# Main.net
KiCad netlist of a schematic drawn in Altium Designer
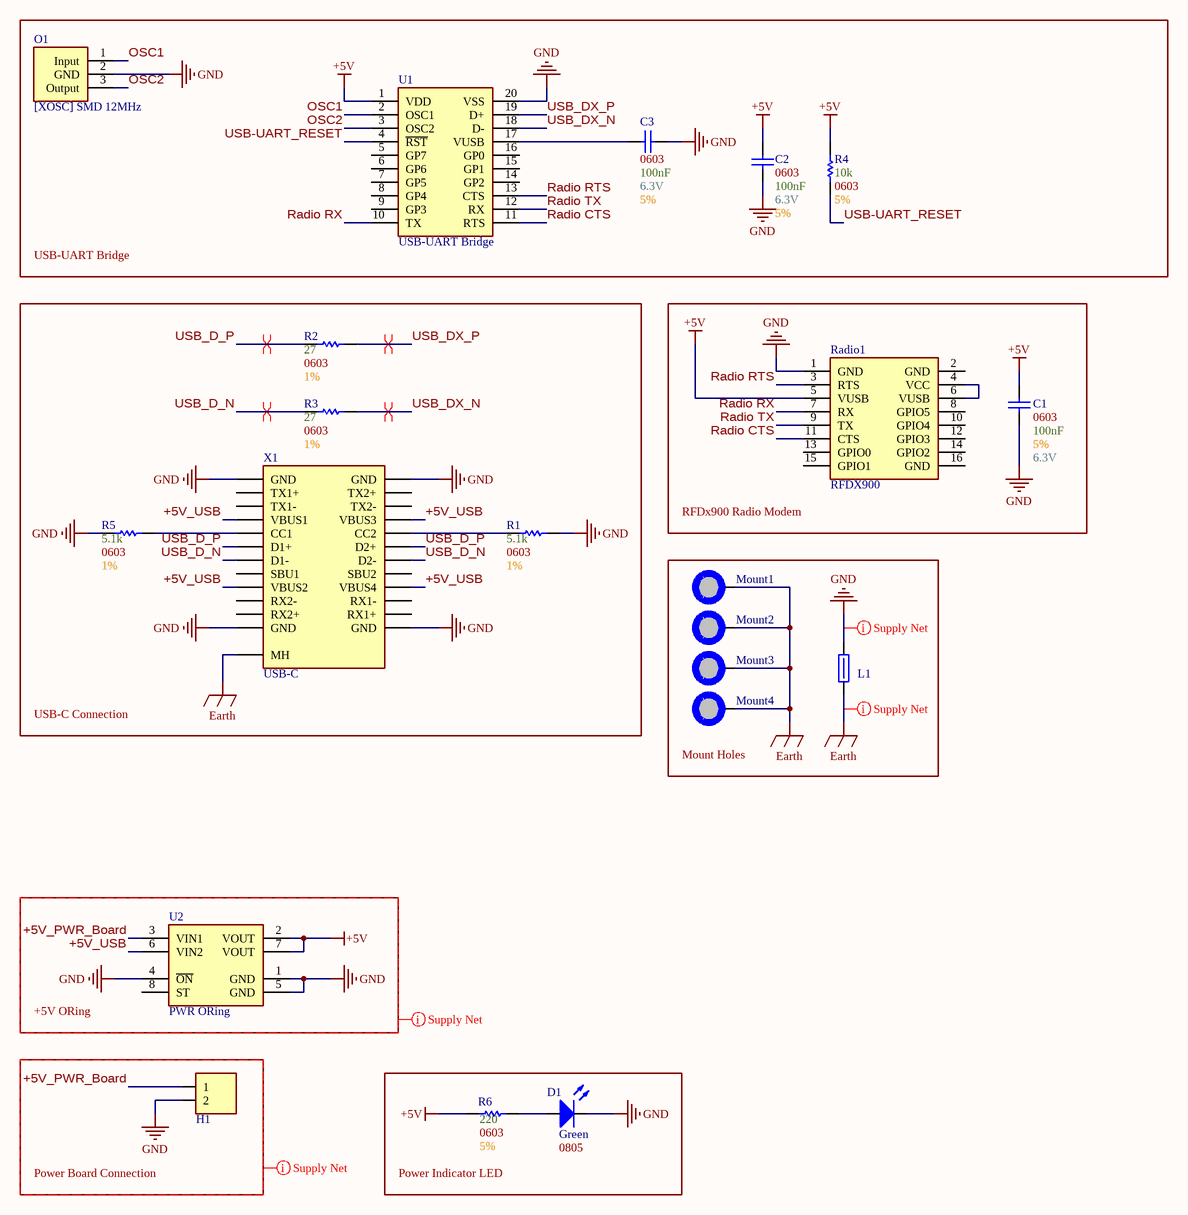
[diagram p0: Main.SchDoc]

(export (version "E")
  (design (tool "Eeschema 10.0.6"))
  (components
    (comp (ref "C1")
      (value "[Cap] SMD Nonpolarized")
      (footprint "[Cap] SMD 0603")
      (fields
        (field (name "SIZE PACKAGE") "0603")
        (field (name "CAPACITANCE") "100nF")
        (field (name "VOLTAGE") "6.3V")
        (field (name "TOLERANCE") "5%")
      )
      (libsource (lib "RADM Components") (part "[Cap] SMD Nonpolarized"))
    )
    (comp (ref "C2")
      (value "[Cap] SMD Nonpolarized")
      (footprint "[Cap] SMD 0603")
      (fields
        (field (name "SIZE PACKAGE") "0603")
        (field (name "CAPACITANCE") "100nF")
        (field (name "VOLTAGE") "6.3V")
        (field (name "TOLERANCE") "5%")
      )
      (libsource (lib "RADM Components") (part "[Cap] SMD Nonpolarized"))
    )
    (comp (ref "C3")
      (value "[Cap] SMD Nonpolarized")
      (footprint "[Cap] SMD 0603")
      (fields
        (field (name "SIZE PACKAGE") "0603")
        (field (name "CAPACITANCE") "100nF")
        (field (name "VOLTAGE") "6.3V")
        (field (name "TOLERANCE") "5%")
      )
      (libsource (lib "RADM Components") (part "[Cap] SMD Nonpolarized"))
    )
    (comp (ref "D1")
      (value "SMD LED")
      (footprint "[LED] SMD 0805")
      (description "Generic")
      (fields (field (name "COLOR") "Green") (field (name "SIZE PACKAGE") "0805"))
      (libsource (lib "RADM Components") (part "[LED] SMD"))
    )
    (comp (ref "H1")
      (value "1x2 Male")
      (footprint "[Header] Shrouded 1x2 Male")
      (description "0705430036\r\nMates with 0050579402")
      (libsource (lib "RADM Connectors") (part "[Header] Shrouded 1x2 Male"))
    )
    (comp (ref "L1")
      (value "652-MH2029-300Y")
      (footprint "[Ferrite] SMD Bead 0805 (1)")
      (libsource (lib "RADM Components") (part "[Ferrite] SMD Ferrite Bead (1)"))
    )
    (comp (ref "Mount1")
      (value "M3 Mount Hole")
      (footprint "[Mount] M3 Mount Hole")
      (description "Place at least 4.5mm from board edge. Plated.")
      (libsource (lib "RADM Connectors") (part "[Mount] M3 Mount Hole"))
    )
    (comp (ref "Mount2")
      (value "M3 Mount Hole")
      (footprint "[Mount] M3 Mount Hole")
      (description "Place at least 4.5mm from board edge. Plated.")
      (libsource (lib "RADM Connectors") (part "[Mount] M3 Mount Hole"))
    )
    (comp (ref "Mount3")
      (value "M3 Mount Hole")
      (footprint "[Mount] M3 Mount Hole")
      (description "Place at least 4.5mm from board edge. Plated.")
      (libsource (lib "RADM Connectors") (part "[Mount] M3 Mount Hole"))
    )
    (comp (ref "Mount4")
      (value "M3 Mount Hole")
      (footprint "[Mount] M3 Mount Hole")
      (description "Place at least 4.5mm from board edge. Plated.")
      (libsource (lib "RADM Connectors") (part "[Mount] M3 Mount Hole"))
    )
    (comp (ref "O1")
      (value "[XOSC] SMD 12MHz")
      (footprint "[XOSC] SMD 12MHz")
      (libsource (lib "RADM Components") (part "[XOSC] SMD 12MHz"))
    )
    (comp (ref "R1")
      (value "[Res] SMD Resistor")
      (footprint "[Res] SMD 0603")
      (description "Generic")
      (fields
        (field (name "TOLERANCE") "1%")
        (field (name "RESISTANCE") "5.1k")
        (field (name "SIZE PACKAGE") "0603")
      )
      (libsource (lib "RADM Components") (part "[Res] SMD Resistor"))
    )
    (comp (ref "R2")
      (value "[Res] SMD Resistor")
      (footprint "[Res] SMD 0603")
      (description "Generic")
      (fields
        (field (name "TOLERANCE") "1%")
        (field (name "RESISTANCE") "27")
        (field (name "SIZE PACKAGE") "0603")
      )
      (libsource (lib "RADM Components") (part "[Res] SMD Resistor"))
    )
    (comp (ref "R3")
      (value "[Res] SMD Resistor")
      (footprint "[Res] SMD 0603")
      (description "Generic")
      (fields
        (field (name "TOLERANCE") "1%")
        (field (name "RESISTANCE") "27")
        (field (name "SIZE PACKAGE") "0603")
      )
      (libsource (lib "RADM Components") (part "[Res] SMD Resistor"))
    )
    (comp (ref "R4")
      (value "[Res] SMD Resistor")
      (footprint "[Res] SMD 0603")
      (description "Generic")
      (fields
        (field (name "RESISTANCE") "10k")
        (field (name "SIZE PACKAGE") "0603")
        (field (name "TOLERANCE") "5%")
      )
      (libsource (lib "RADM Components") (part "[Res] SMD Resistor"))
    )
    (comp (ref "R5")
      (value "[Res] SMD Resistor")
      (footprint "[Res] SMD 0603")
      (description "Generic")
      (fields
        (field (name "TOLERANCE") "1%")
        (field (name "RESISTANCE") "5.1k")
        (field (name "SIZE PACKAGE") "0603")
      )
      (libsource (lib "RADM Components") (part "[Res] SMD Resistor"))
    )
    (comp (ref "R6")
      (value "[Res] SMD Resistor")
      (footprint "[Res] SMD 0603")
      (description "Generic")
      (fields
        (field (name "RESISTANCE") "220")
        (field (name "SIZE PACKAGE") "0603")
        (field (name "TOLERANCE") "5%")
      )
      (libsource (lib "RADM Components") (part "[Res] SMD Resistor"))
    )
    (comp (ref "Radio1")
      (value "RFDX900")
      (footprint "[Device] RFDX900 Radio")
      (description "RFDX900 Long-Range RF Module")
      (libsource (lib "RADM Components") (part "[Device] RFDX900 Radio"))
    )
    (comp (ref "U1")
      (value "USB-UART Bridge")
      (footprint "[IC] USB-UART Bridge")
      (description "MCP2200T-I/SO")
      (libsource (lib "RADM Components") (part "[IC] USB-UART Bridge"))
    )
    (comp (ref "U2")
      (value "PWR ORing")
      (footprint "[IC] Power ORing Controller")
      (libsource (lib "RADM Components") (part "[IC] Power ORing Controller"))
    )
    (comp (ref "X1")
      (value "USB-C")
      (footprint "[Port] USB-C")
      (libsource (lib "RADM Connectors") (part "[Port] USB Type-C"))
    )
  )
  (nets
    (net (code "1") (name "+5V") (class "Default")
      (node (ref "C1") (pin "2") (pinfunction "2_2") (pintype "passive"))
      (node (ref "C2") (pin "2") (pinfunction "2_2") (pintype "passive"))
      (node (ref "R4") (pin "2") (pinfunction "2_2") (pintype "passive"))
      (node (ref "R6") (pin "2") (pinfunction "2_2") (pintype "passive"))
      (node (ref "Radio1") (pin "5") (pinfunction "VUSB_5") (pintype "passive"))
      (node (ref "U1") (pin "1") (pinfunction "VDD_1") (pintype "passive"))
      (node (ref "U2") (pin "2") (pinfunction "VOUT_2") (pintype "passive"))
      (node (ref "U2") (pin "7") (pinfunction "VOUT_7") (pintype "passive"))
    )
    (net (code "2") (name "/+5V_PWR_Board") (class "Default")
      (node (ref "H1") (pin "1") (pinfunction "1_1") (pintype "passive"))
      (node (ref "U2") (pin "3") (pinfunction "VIN1_3") (pintype "passive"))
    )
    (net (code "3") (name "/+5V_USB") (class "Default")
      (node (ref "U2") (pin "6") (pinfunction "VIN2_6") (pintype "passive"))
      (node (ref "X1") (pin "A4") (pinfunction "VBUS1_A4") (pintype "passive"))
      (node (ref "X1") (pin "A9") (pinfunction "VBUS2_A9") (pintype "passive"))
      (node (ref "X1") (pin "B4") (pinfunction "VBUS3_B4") (pintype "passive"))
      (node (ref "X1") (pin "B9") (pinfunction "VBUS4_B9") (pintype "passive"))
    )
    (net (code "4") (name "/OSC1") (class "Default")
      (node (ref "O1") (pin "1") (pinfunction "Input_1") (pintype "passive"))
      (node (ref "U1") (pin "2") (pinfunction "OSC1_2") (pintype "passive"))
    )
    (net (code "5") (name "/OSC2") (class "Default")
      (node (ref "O1") (pin "3") (pinfunction "Output_3") (pintype "passive"))
      (node (ref "U1") (pin "3") (pinfunction "OSC2_3") (pintype "passive"))
    )
    (net (code "6") (name "/Radio CTS") (class "Default")
      (node (ref "Radio1") (pin "11") (pinfunction "CTS_11") (pintype "passive"))
      (node (ref "U1") (pin "11") (pinfunction "RTS_11") (pintype "passive"))
    )
    (net (code "7") (name "/Radio RTS") (class "Default")
      (node (ref "Radio1") (pin "3") (pinfunction "RTS_3") (pintype "passive"))
      (node (ref "U1") (pin "13") (pinfunction "CTS_13") (pintype "passive"))
    )
    (net (code "8") (name "/Radio RX") (class "Default")
      (node (ref "Radio1") (pin "7") (pinfunction "RX_7") (pintype "passive"))
      (node (ref "U1") (pin "10") (pinfunction "TX_10") (pintype "passive"))
    )
    (net (code "9") (name "/Radio TX") (class "Default")
      (node (ref "Radio1") (pin "9") (pinfunction "TX_9") (pintype "passive"))
      (node (ref "U1") (pin "12") (pinfunction "RX_12") (pintype "passive"))
    )
    (net (code "10") (name "/USB-UART_RESET") (class "Default")
      (node (ref "R4") (pin "1") (pinfunction "1_1") (pintype "passive"))
      (node (ref "U1") (pin "4") (pinfunction "RST_4") (pintype "passive"))
    )
    (net (code "11") (name "/USB_DX_N") (class "Default")
      (node (ref "R3") (pin "2") (pinfunction "2_2") (pintype "passive"))
      (node (ref "U1") (pin "18") (pinfunction "D-_18") (pintype "passive"))
    )
    (net (code "12") (name "/USB_DX_P") (class "Default")
      (node (ref "R2") (pin "2") (pinfunction "2_2") (pintype "passive"))
      (node (ref "U1") (pin "19") (pinfunction "D+_19") (pintype "passive"))
    )
    (net (code "13") (name "/USB_D_N") (class "Default")
      (node (ref "R3") (pin "1") (pinfunction "1_1") (pintype "passive"))
      (node (ref "X1") (pin "A7") (pinfunction "D1-_A7") (pintype "passive"))
      (node (ref "X1") (pin "B7") (pinfunction "D2-_B7") (pintype "passive"))
    )
    (net (code "14") (name "/USB_D_P") (class "Default")
      (node (ref "R2") (pin "1") (pinfunction "1_1") (pintype "passive"))
      (node (ref "X1") (pin "A6") (pinfunction "D1+_A6") (pintype "passive"))
      (node (ref "X1") (pin "B6") (pinfunction "D2+_B6") (pintype "passive"))
    )
    (net (code "15") (name "Earth") (class "Default")
      (node (ref "L1") (pin "1") (pinfunction "1_1") (pintype "passive"))
      (node (ref "Mount1") (pin "1") (pintype "power_in"))
      (node (ref "Mount2") (pin "1") (pintype "power_in"))
      (node (ref "Mount3") (pin "1") (pintype "power_in"))
      (node (ref "Mount4") (pin "1") (pintype "power_in"))
      (node (ref "X1") (pin "MH") (pinfunction "MH_MH") (pintype "passive"))
    )
    (net (code "16") (name "GND") (class "Default")
      (node (ref "C1") (pin "1") (pinfunction "1_1") (pintype "passive"))
      (node (ref "C2") (pin "1") (pinfunction "1_1") (pintype "passive"))
      (node (ref "C3") (pin "1") (pinfunction "1_1") (pintype "passive"))
      (node (ref "D1") (pin "2") (pinfunction "Cathode_2") (pintype "passive"))
      (node (ref "H1") (pin "2") (pinfunction "2_2") (pintype "passive"))
      (node (ref "L1") (pin "2") (pinfunction "2_2") (pintype "passive"))
      (node (ref "O1") (pin "2") (pinfunction "GND_2") (pintype "passive"))
      (node (ref "R1") (pin "2") (pinfunction "2_2") (pintype "passive"))
      (node (ref "R5") (pin "1") (pinfunction "1_1") (pintype "passive"))
      (node (ref "Radio1") (pin "1") (pinfunction "GND_1") (pintype "passive"))
      (node (ref "U1") (pin "20") (pinfunction "VSS_20") (pintype "passive"))
      (node (ref "U2") (pin "1") (pinfunction "GND_1") (pintype "passive"))
      (node (ref "U2") (pin "4") (pinfunction "~{ON}_4") (pintype "passive"))
      (node (ref "U2") (pin "5") (pinfunction "GND_5") (pintype "passive"))
      (node (ref "X1") (pin "A1") (pinfunction "GND_A1") (pintype "passive"))
      (node (ref "X1") (pin "A12") (pinfunction "GND_A12") (pintype "passive"))
      (node (ref "X1") (pin "B1") (pinfunction "GND_B1") (pintype "passive"))
      (node (ref "X1") (pin "B12") (pinfunction "GND_B12") (pintype "passive"))
    )
    (net (code "17") (name "Net-(D1-Anode)") (class "Default")
      (node (ref "D1") (pin "1") (pinfunction "Anode_1") (pintype "passive"))
      (node (ref "R6") (pin "1") (pinfunction "1_1") (pintype "passive"))
    )
    (net (code "18") (name "Net-(Radio1-VCC)") (class "Default")
      (node (ref "Radio1") (pin "4") (pinfunction "VCC_4") (pintype "passive"))
      (node (ref "Radio1") (pin "6") (pinfunction "VUSB_6") (pintype "passive"))
    )
    (net (code "19") (name "Net-(U1-VUSB)") (class "Default")
      (node (ref "C3") (pin "2") (pinfunction "2_2") (pintype "passive"))
      (node (ref "U1") (pin "17") (pinfunction "VUSB_17") (pintype "passive"))
    )
    (net (code "20") (name "Net-(X1-CC1)") (class "Default")
      (node (ref "R5") (pin "2") (pinfunction "2_2") (pintype "passive"))
      (node (ref "X1") (pin "A5") (pinfunction "CC1_A5") (pintype "passive"))
    )
    (net (code "21") (name "Net-(X1-CC2)") (class "Default")
      (node (ref "R1") (pin "1") (pinfunction "1_1") (pintype "passive"))
      (node (ref "X1") (pin "B5") (pinfunction "CC2_B5") (pintype "passive"))
    )
    (net (code "22") (name "unconnected-(Radio1-GND-Pad2)") (class "Default")
      (node (ref "Radio1") (pin "2") (pinfunction "GND_2") (pintype "passive"))
    )
    (net (code "23") (name "unconnected-(Radio1-GND-Pad16)") (class "Default")
      (node (ref "Radio1") (pin "16") (pinfunction "GND_16") (pintype "passive"))
    )
    (net (code "24") (name "unconnected-(Radio1-GPIO0-Pad13)") (class "Default")
      (node (ref "Radio1") (pin "13") (pinfunction "GPIO0_13") (pintype "passive"))
    )
    (net (code "25") (name "unconnected-(Radio1-GPIO1-Pad15)") (class "Default")
      (node (ref "Radio1") (pin "15") (pinfunction "GPIO1_15") (pintype "passive"))
    )
    (net (code "26") (name "unconnected-(Radio1-GPIO2-Pad14)") (class "Default")
      (node (ref "Radio1") (pin "14") (pinfunction "GPIO2_14") (pintype "passive"))
    )
    (net (code "27") (name "unconnected-(Radio1-GPIO3-Pad12)") (class "Default")
      (node (ref "Radio1") (pin "12") (pinfunction "GPIO3_12") (pintype "passive"))
    )
    (net (code "28") (name "unconnected-(Radio1-GPIO4-Pad10)") (class "Default")
      (node (ref "Radio1") (pin "10") (pinfunction "GPIO4_10") (pintype "passive"))
    )
    (net (code "29") (name "unconnected-(Radio1-GPIO5-Pad8)") (class "Default")
      (node (ref "Radio1") (pin "8") (pinfunction "GPIO5_8") (pintype "passive"))
    )
    (net (code "30") (name "unconnected-(U1-GP0-Pad16)") (class "Default")
      (node (ref "U1") (pin "16") (pinfunction "GP0_16") (pintype "passive"))
    )
    (net (code "31") (name "unconnected-(U1-GP1-Pad15)") (class "Default")
      (node (ref "U1") (pin "15") (pinfunction "GP1_15") (pintype "passive"))
    )
    (net (code "32") (name "unconnected-(U1-GP2-Pad14)") (class "Default")
      (node (ref "U1") (pin "14") (pinfunction "GP2_14") (pintype "passive"))
    )
    (net (code "33") (name "unconnected-(U1-GP3-Pad9)") (class "Default")
      (node (ref "U1") (pin "9") (pinfunction "GP3_9") (pintype "passive"))
    )
    (net (code "34") (name "unconnected-(U1-GP4-Pad8)") (class "Default")
      (node (ref "U1") (pin "8") (pinfunction "GP4_8") (pintype "passive"))
    )
    (net (code "35") (name "unconnected-(U1-GP5-Pad7)") (class "Default")
      (node (ref "U1") (pin "7") (pinfunction "GP5_7") (pintype "passive"))
    )
    (net (code "36") (name "unconnected-(U1-GP6-Pad6)") (class "Default")
      (node (ref "U1") (pin "6") (pinfunction "GP6_6") (pintype "passive"))
    )
    (net (code "37") (name "unconnected-(U1-GP7-Pad5)") (class "Default")
      (node (ref "U1") (pin "5") (pinfunction "GP7_5") (pintype "passive"))
    )
    (net (code "38") (name "unconnected-(U2-ST-Pad8)") (class "Default")
      (node (ref "U2") (pin "8") (pinfunction "ST_8") (pintype "passive"))
    )
    (net (code "39") (name "unconnected-(X1-RX1+-PadB11)") (class "Default")
      (node (ref "X1") (pin "B11") (pinfunction "RX1+_B11") (pintype "passive"))
    )
    (net (code "40") (name "unconnected-(X1-RX1--PadB10)") (class "Default")
      (node (ref "X1") (pin "B10") (pinfunction "RX1-_B10") (pintype "passive"))
    )
    (net (code "41") (name "unconnected-(X1-RX2+-PadA11)") (class "Default")
      (node (ref "X1") (pin "A11") (pinfunction "RX2+_A11") (pintype "passive"))
    )
    (net (code "42") (name "unconnected-(X1-RX2--PadA10)") (class "Default")
      (node (ref "X1") (pin "A10") (pinfunction "RX2-_A10") (pintype "passive"))
    )
    (net (code "43") (name "unconnected-(X1-SBU1-PadA8)") (class "Default")
      (node (ref "X1") (pin "A8") (pinfunction "SBU1_A8") (pintype "passive"))
    )
    (net (code "44") (name "unconnected-(X1-SBU2-PadB8)") (class "Default")
      (node (ref "X1") (pin "B8") (pinfunction "SBU2_B8") (pintype "passive"))
    )
    (net (code "45") (name "unconnected-(X1-TX1+-PadA2)") (class "Default")
      (node (ref "X1") (pin "A2") (pinfunction "TX1+_A2") (pintype "passive"))
    )
    (net (code "46") (name "unconnected-(X1-TX1--PadA3)") (class "Default")
      (node (ref "X1") (pin "A3") (pinfunction "TX1-_A3") (pintype "passive"))
    )
    (net (code "47") (name "unconnected-(X1-TX2+-PadB2)") (class "Default")
      (node (ref "X1") (pin "B2") (pinfunction "TX2+_B2") (pintype "passive"))
    )
    (net (code "48") (name "unconnected-(X1-TX2--PadB3)") (class "Default")
      (node (ref "X1") (pin "B3") (pinfunction "TX2-_B3") (pintype "passive"))
    )
  )
)
